# 03_USB_TO_UART.net
KiCad netlist of a schematic drawn in Altium Designer
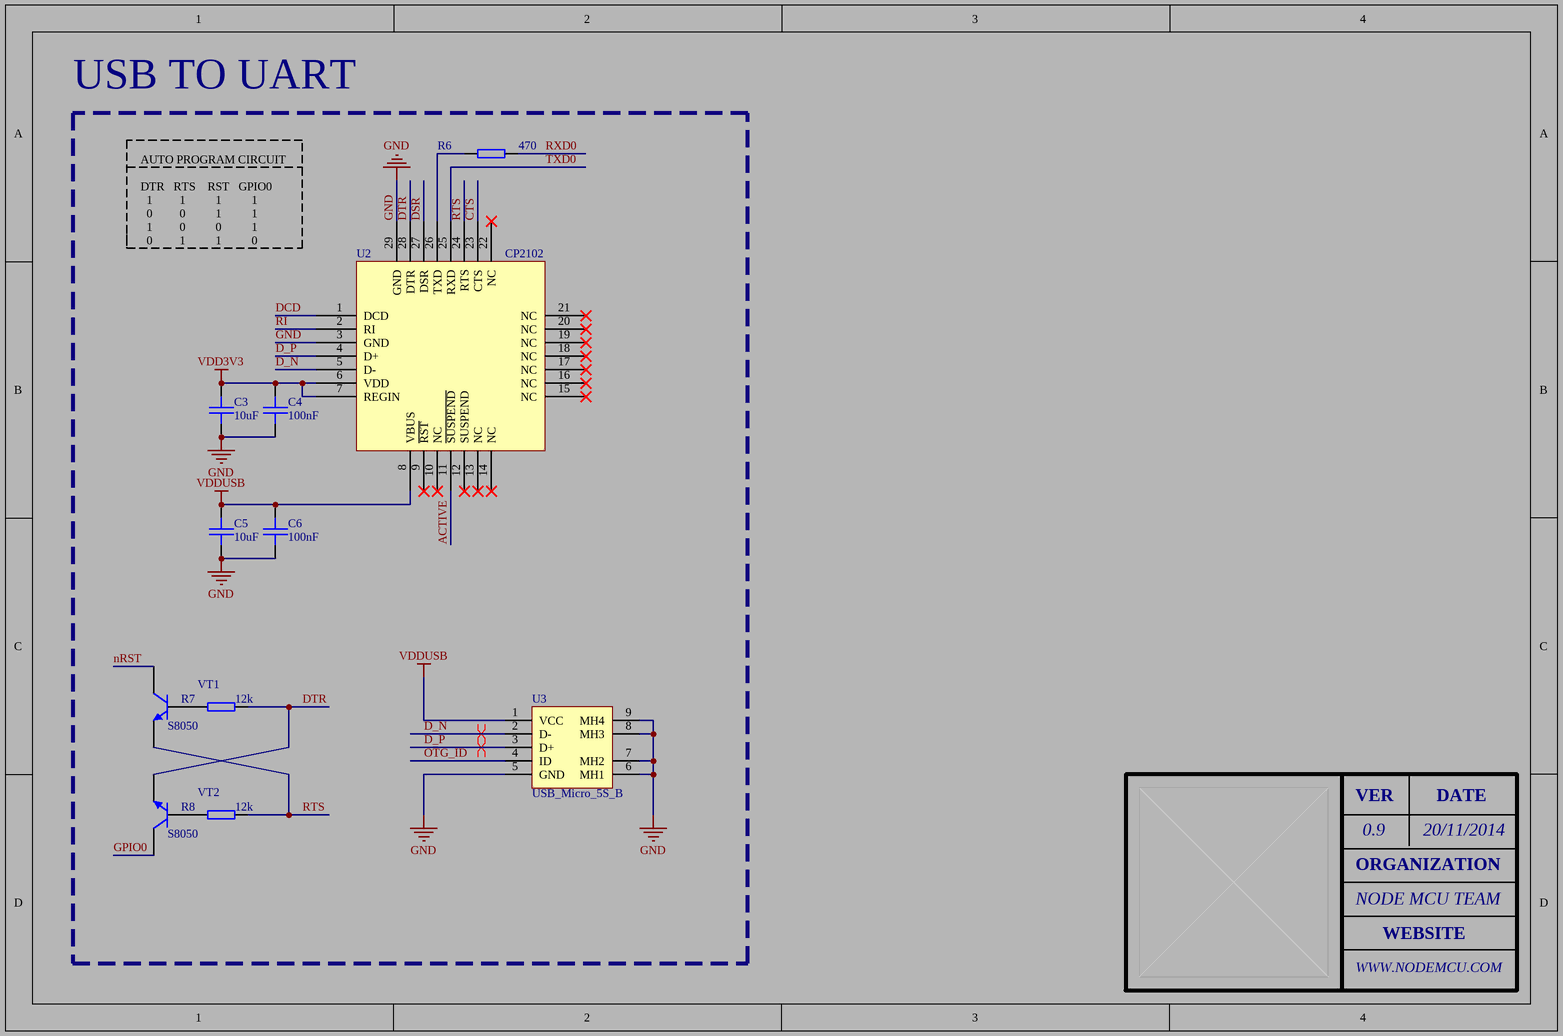
[diagram p0: 03_USB_TO_UART.SchDoc]

(export (version "E")
  (design (tool "Eeschema 10.0.6"))
  (components
    (comp (ref "C3")
      (value "10uF")
      (footprint "SMT_C_0402")
      (description "Surface mount capacitor 0402")
      (libsource (lib "Vowstar_Basic_Device") (part "SMT_C_0402"))
    )
    (comp (ref "C4")
      (value "100nF")
      (footprint "SMT_C_0402")
      (description "Surface mount capacitor 0402")
      (libsource (lib "Vowstar_Basic_Device") (part "SMT_C_0402"))
    )
    (comp (ref "C5")
      (value "10uF")
      (footprint "SMT_C_0402")
      (description "Surface mount capacitor 0402")
      (libsource (lib "Vowstar_Basic_Device") (part "SMT_C_0402"))
    )
    (comp (ref "C6")
      (value "100nF")
      (footprint "SMT_C_0402")
      (description "Surface mount capacitor 0402")
      (libsource (lib "Vowstar_Basic_Device") (part "SMT_C_0402"))
    )
    (comp (ref "R6")
      (value "470")
      (footprint "SMT_R_0402")
      (description "Surface mount resistor 0402")
      (libsource (lib "Vowstar_Basic_Device") (part "SMT_R_0402"))
    )
    (comp (ref "R7")
      (value "12k")
      (footprint "SMT_R_0402")
      (description "Surface mount resistor 0402")
      (libsource (lib "Vowstar_Basic_Device") (part "SMT_R_0402"))
    )
    (comp (ref "R8")
      (value "12k")
      (footprint "SMT_R_0402")
      (description "Surface mount resistor 0402")
      (libsource (lib "Vowstar_Basic_Device") (part "SMT_R_0402"))
    )
    (comp (ref "U2")
      (value "CP2102")
      (footprint "CP2102")
      (libsource (lib "Vowstar_IC_General") (part "CP2102"))
    )
    (comp (ref "U3")
      (value "USB_Micro_5S_B")
      (footprint "USB_MICRO_5S_B")
      (description "USB micro female SMT with 4 fixed foot")
      (libsource (lib "Vowstar_Connector") (part "USB_Micro_5S_B"))
    )
    (comp (ref "VT1")
      (value "S8050")
      (footprint "SMT_TRIODE_NPN")
      (description "Surface mount NPN transistor, package SOT-23")
      (libsource (lib "Vowstar_Basic_Device") (part "SMT_TRIODE_NPN"))
    )
    (comp (ref "VT2")
      (value "S8050")
      (footprint "SMT_TRIODE_NPN")
      (description "Surface mount NPN transistor, package SOT-23")
      (libsource (lib "Vowstar_Basic_Device") (part "SMT_TRIODE_NPN"))
    )
  )
  (nets
    (net (code "1") (name "/ACTIVE") (class "Default")
      (node (ref "U2") (pin "11") (pinfunction "~{SUSPEND}_11") (pintype "passive"))
    )
    (net (code "2") (name "/CTS") (class "Default")
      (node (ref "U2") (pin "23") (pinfunction "CTS_23") (pintype "passive"))
    )
    (net (code "3") (name "/DCD") (class "Default")
      (node (ref "U2") (pin "1") (pinfunction "DCD_1") (pintype "passive"))
    )
    (net (code "4") (name "/DSR") (class "Default")
      (node (ref "U2") (pin "27") (pinfunction "DSR_27") (pintype "passive"))
    )
    (net (code "5") (name "/DTR") (class "Default")
      (node (ref "R7") (pin "2") (pinfunction "2_2") (pintype "passive"))
      (node (ref "U2") (pin "28") (pinfunction "DTR_28") (pintype "passive"))
      (node (ref "VT2") (pin "2") (pinfunction "E_2") (pintype "passive"))
    )
    (net (code "6") (name "/D_N") (class "Default")
      (node (ref "U2") (pin "5") (pinfunction "D-_5") (pintype "passive"))
      (node (ref "U3") (pin "2") (pinfunction "D-_2") (pintype "passive"))
    )
    (net (code "7") (name "/D_P") (class "Default")
      (node (ref "U2") (pin "4") (pinfunction "D+_4") (pintype "passive"))
      (node (ref "U3") (pin "3") (pinfunction "D+_3") (pintype "passive"))
    )
    (net (code "8") (name "/GPIO0") (class "Default")
      (node (ref "VT2") (pin "3") (pinfunction "C_3") (pintype "passive"))
    )
    (net (code "9") (name "/OTG_ID") (class "Default")
      (node (ref "U3") (pin "4") (pinfunction "ID_4") (pintype "passive"))
    )
    (net (code "10") (name "/RI") (class "Default")
      (node (ref "U2") (pin "2") (pinfunction "RI_2") (pintype "passive"))
    )
    (net (code "11") (name "/RTS") (class "Default")
      (node (ref "R8") (pin "2") (pinfunction "2_2") (pintype "passive"))
      (node (ref "U2") (pin "24") (pinfunction "RTS_24") (pintype "passive"))
      (node (ref "VT1") (pin "2") (pinfunction "E_2") (pintype "passive"))
    )
    (net (code "12") (name "/RXD0") (class "Default")
      (node (ref "R6") (pin "2") (pinfunction "2_2") (pintype "passive"))
    )
    (net (code "13") (name "/TXD0") (class "Default")
      (node (ref "U2") (pin "25") (pinfunction "RXD_25") (pintype "passive"))
    )
    (net (code "14") (name "/nRST") (class "Default")
      (node (ref "VT1") (pin "3") (pinfunction "C_3") (pintype "passive"))
    )
    (net (code "15") (name "GND") (class "Default")
      (node (ref "C3") (pin "2") (pinfunction "2_2") (pintype "passive"))
      (node (ref "C4") (pin "2") (pinfunction "2_2") (pintype "passive"))
      (node (ref "C5") (pin "2") (pinfunction "2_2") (pintype "passive"))
      (node (ref "C6") (pin "2") (pinfunction "2_2") (pintype "passive"))
      (node (ref "U2") (pin "29") (pinfunction "GND_29") (pintype "passive"))
      (node (ref "U2") (pin "3") (pinfunction "GND_3") (pintype "passive"))
      (node (ref "U3") (pin "5") (pinfunction "GND_5") (pintype "passive"))
      (node (ref "U3") (pin "6") (pinfunction "MH1_6") (pintype "passive"))
      (node (ref "U3") (pin "7") (pinfunction "MH2_7") (pintype "passive"))
      (node (ref "U3") (pin "8") (pinfunction "MH3_8") (pintype "passive"))
      (node (ref "U3") (pin "9") (pinfunction "MH4_9") (pintype "passive"))
    )
    (net (code "16") (name "Net-(U2-TXD)") (class "Default")
      (node (ref "R6") (pin "1") (pinfunction "1_1") (pintype "passive"))
      (node (ref "U2") (pin "26") (pinfunction "TXD_26") (pintype "passive"))
    )
    (net (code "17") (name "Net-(VT1-B)") (class "Default")
      (node (ref "R7") (pin "1") (pinfunction "1_1") (pintype "passive"))
      (node (ref "VT1") (pin "1") (pinfunction "B_1") (pintype "passive"))
    )
    (net (code "18") (name "Net-(VT2-B)") (class "Default")
      (node (ref "R8") (pin "1") (pinfunction "1_1") (pintype "passive"))
      (node (ref "VT2") (pin "1") (pinfunction "B_1") (pintype "passive"))
    )
    (net (code "19") (name "VDD3V3") (class "Default")
      (node (ref "C3") (pin "1") (pinfunction "1_1") (pintype "passive"))
      (node (ref "C4") (pin "1") (pinfunction "1_1") (pintype "passive"))
      (node (ref "U2") (pin "6") (pinfunction "VDD_6") (pintype "passive"))
      (node (ref "U2") (pin "7") (pinfunction "REGIN_7") (pintype "passive"))
    )
    (net (code "20") (name "VDDUSB") (class "Default")
      (node (ref "C5") (pin "1") (pinfunction "1_1") (pintype "passive"))
      (node (ref "C6") (pin "1") (pinfunction "1_1") (pintype "passive"))
      (node (ref "U2") (pin "8") (pinfunction "VBUS_8") (pintype "passive"))
      (node (ref "U3") (pin "1") (pinfunction "VCC_1") (pintype "passive"))
    )
    (net (code "21") (name "unconnected-(U2-NC-Pad10)") (class "Default")
      (node (ref "U2") (pin "10") (pinfunction "NC_10") (pintype "passive+no_connect"))
    )
    (net (code "22") (name "unconnected-(U2-NC-Pad13)") (class "Default")
      (node (ref "U2") (pin "13") (pinfunction "NC_13") (pintype "passive+no_connect"))
    )
    (net (code "23") (name "unconnected-(U2-NC-Pad14)") (class "Default")
      (node (ref "U2") (pin "14") (pinfunction "NC_14") (pintype "passive+no_connect"))
    )
    (net (code "24") (name "unconnected-(U2-NC-Pad15)") (class "Default")
      (node (ref "U2") (pin "15") (pinfunction "NC_15") (pintype "passive+no_connect"))
    )
    (net (code "25") (name "unconnected-(U2-NC-Pad16)") (class "Default")
      (node (ref "U2") (pin "16") (pinfunction "NC_16") (pintype "passive+no_connect"))
    )
    (net (code "26") (name "unconnected-(U2-NC-Pad17)") (class "Default")
      (node (ref "U2") (pin "17") (pinfunction "NC_17") (pintype "passive+no_connect"))
    )
    (net (code "27") (name "unconnected-(U2-NC-Pad18)") (class "Default")
      (node (ref "U2") (pin "18") (pinfunction "NC_18") (pintype "passive+no_connect"))
    )
    (net (code "28") (name "unconnected-(U2-NC-Pad19)") (class "Default")
      (node (ref "U2") (pin "19") (pinfunction "NC_19") (pintype "passive+no_connect"))
    )
    (net (code "29") (name "unconnected-(U2-NC-Pad20)") (class "Default")
      (node (ref "U2") (pin "20") (pinfunction "NC_20") (pintype "passive+no_connect"))
    )
    (net (code "30") (name "unconnected-(U2-NC-Pad21)") (class "Default")
      (node (ref "U2") (pin "21") (pinfunction "NC_21") (pintype "passive+no_connect"))
    )
    (net (code "31") (name "unconnected-(U2-NC-Pad22)") (class "Default")
      (node (ref "U2") (pin "22") (pinfunction "NC_22") (pintype "passive+no_connect"))
    )
    (net (code "32") (name "unconnected-(U2-SUSPEND-Pad12)") (class "Default")
      (node (ref "U2") (pin "12") (pinfunction "SUSPEND_12") (pintype "passive+no_connect"))
    )
    (net (code "33") (name "unconnected-(U2-~{RST}-Pad9)") (class "Default")
      (node (ref "U2") (pin "9") (pinfunction "~{RST}_9") (pintype "passive+no_connect"))
    )
  )
)
